# MODULE.net
KiCad netlist of a schematic drawn in Altium Designer
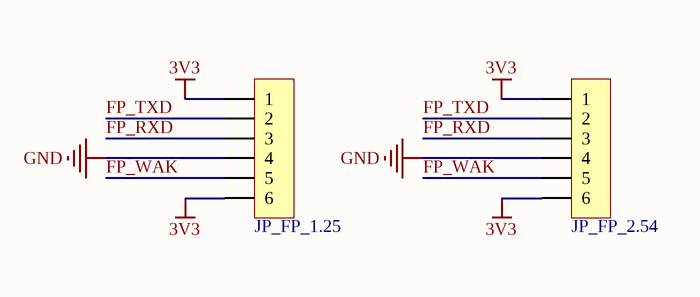
[diagram p0: MODULE.SchDoc]

(export (version "E")
  (design (tool "Eeschema 10.0.6"))
  (components
    (comp (ref "JP_FP_1.25")
      (value "HDR-1X6")
      (footprint "MX 1.25-WS-6P")
      (description "6P接插件")
      (fields (field (name "版权归属") "源创客"))
      (libsource (lib "4.2   - 接插件-脚距1.25") (part "Header 6"))
    )
    (comp (ref "JP_FP_2.54")
      (value "HDR-1X6")
      (footprint "HDR2.54-LI-6P")
      (description "6P接插件")
      (fields (field (name "版权归属") "源创客"))
      (libsource (lib "4.5   - 接插件-脚距2.54") (part "Header 6"))
    )
  )
  (nets
    (net (code "1") (name "/FP_RXD") (class "Default")
      (node (ref "JP_FP_1.25") (pin "3") (pinfunction "3_3") (pintype "passive"))
      (node (ref "JP_FP_2.54") (pin "3") (pinfunction "3_3") (pintype "passive"))
    )
    (net (code "2") (name "/FP_TXD") (class "Default")
      (node (ref "JP_FP_1.25") (pin "2") (pinfunction "2_2") (pintype "passive"))
      (node (ref "JP_FP_2.54") (pin "2") (pinfunction "2_2") (pintype "passive"))
    )
    (net (code "3") (name "/FP_WAK") (class "Default")
      (node (ref "JP_FP_1.25") (pin "5") (pinfunction "5_5") (pintype "passive"))
      (node (ref "JP_FP_2.54") (pin "5") (pinfunction "5_5") (pintype "passive"))
    )
    (net (code "4") (name "3V3") (class "Default")
      (node (ref "JP_FP_1.25") (pin "1") (pinfunction "1_1") (pintype "passive"))
      (node (ref "JP_FP_1.25") (pin "6") (pinfunction "6_6") (pintype "passive"))
      (node (ref "JP_FP_2.54") (pin "1") (pinfunction "1_1") (pintype "passive"))
      (node (ref "JP_FP_2.54") (pin "6") (pinfunction "6_6") (pintype "passive"))
    )
    (net (code "5") (name "GND") (class "Default")
      (node (ref "JP_FP_1.25") (pin "4") (pinfunction "4_4") (pintype "passive"))
      (node (ref "JP_FP_2.54") (pin "4") (pinfunction "4_4") (pintype "passive"))
    )
  )
)
